# DaughterBoard.net
KiCad netlist of a schematic drawn in Altium Designer
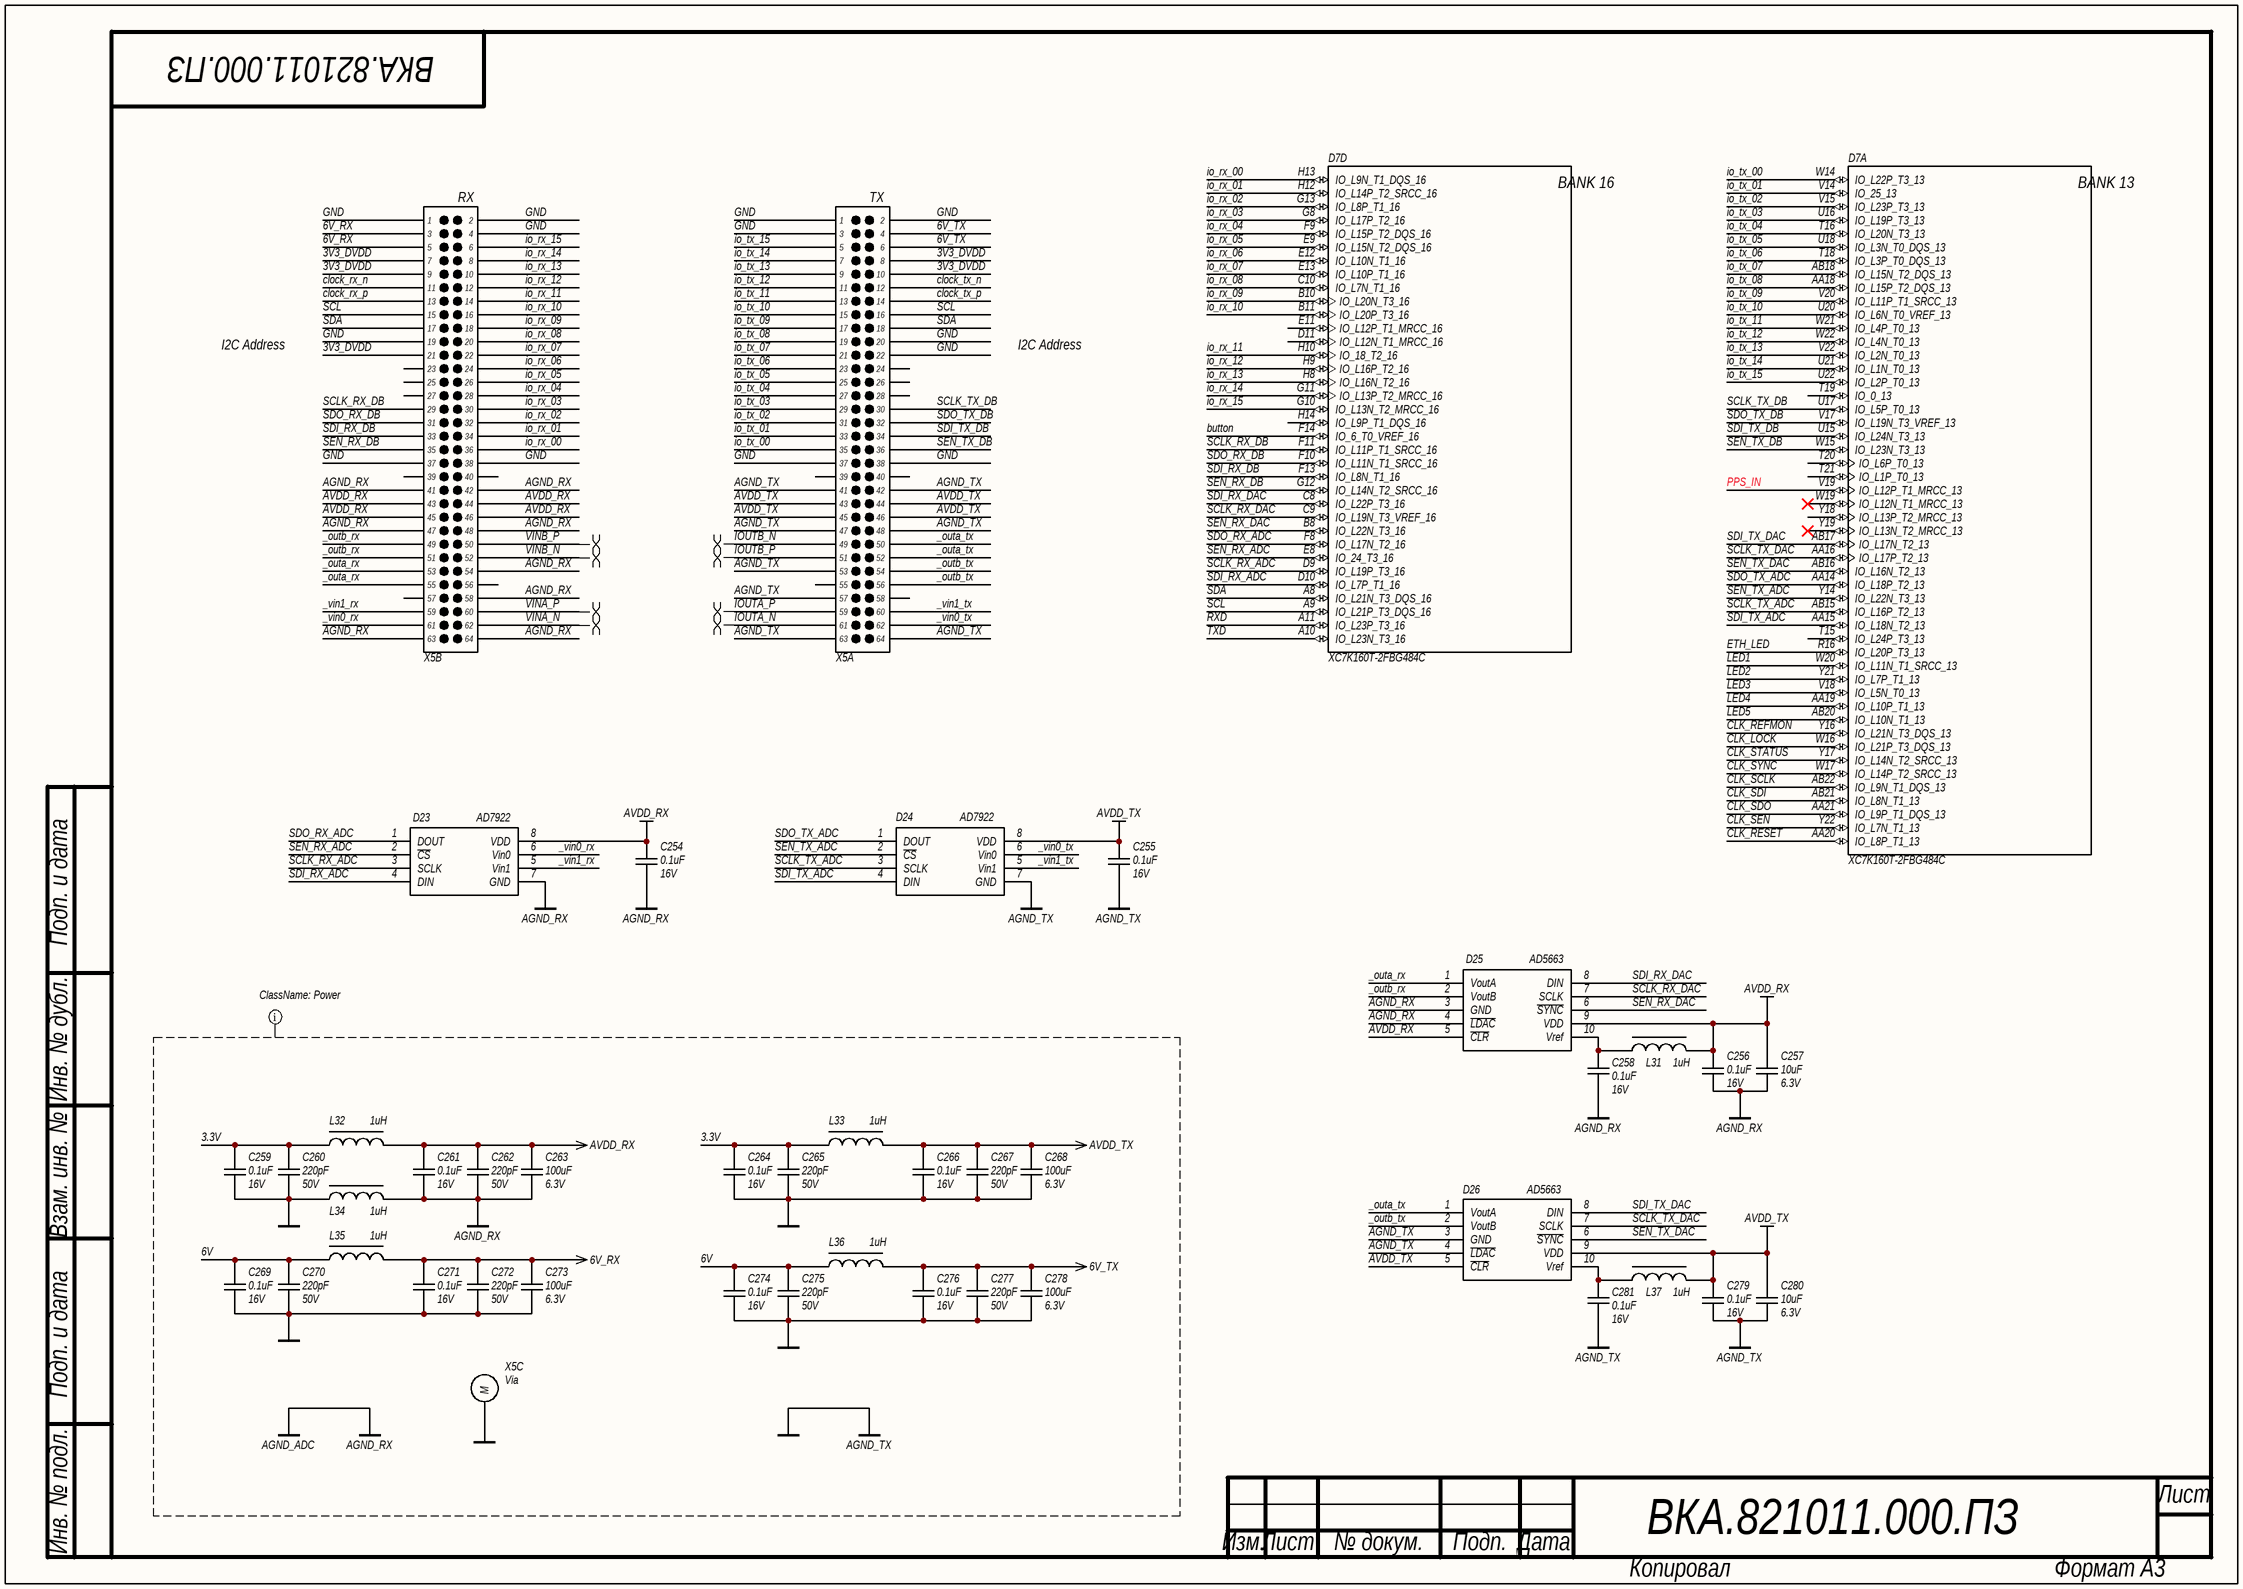
[diagram p0: DaughterBoard.SchDoc]

(export (version "E")
  (design (tool "Eeschema 10.0.6"))
  (components
    (comp (ref "C254")
      (value "0.1uF")
      (footprint "C0402")
      (description "SMD Capacitor")
      (fields
        (field (name "MANUFACTURER") "Murata")
        (field (name "TOLERANCE") "10%")
        (field (name "VOLTAGE") "16V")
      )
      (libsource (lib "Kintex_SDR") (part "CAP"))
    )
    (comp (ref "C255")
      (value "0.1uF")
      (footprint "C0402")
      (description "SMD Capacitor")
      (fields
        (field (name "MANUFACTURER") "Murata")
        (field (name "TOLERANCE") "10%")
        (field (name "VOLTAGE") "16V")
      )
      (libsource (lib "Kintex_SDR") (part "CAP"))
    )
    (comp (ref "C256")
      (value "0.1uF")
      (footprint "C0402")
      (description "SMD Capacitor")
      (fields
        (field (name "MANUFACTURER") "Murata")
        (field (name "TOLERANCE") "10%")
        (field (name "VOLTAGE") "16V")
      )
      (libsource (lib "Kintex_SDR") (part "CAP"))
    )
    (comp (ref "C257")
      (value "10uF")
      (footprint "C0603")
      (description "SMD Capacitor")
      (fields
        (field (name "MANUFACTURER") "Murata")
        (field (name "TOLERANCE") "10%")
        (field (name "VOLTAGE") "6.3V")
      )
      (libsource (lib "Kintex_SDR") (part "CAP"))
    )
    (comp (ref "C258")
      (value "0.1uF")
      (footprint "C0402")
      (description "SMD Capacitor")
      (fields
        (field (name "MANUFACTURER") "Murata")
        (field (name "TOLERANCE") "10%")
        (field (name "VOLTAGE") "16V")
      )
      (libsource (lib "Kintex_SDR") (part "CAP"))
    )
    (comp (ref "C259")
      (value "0.1uF")
      (footprint "C0603")
      (description "SMD Capacitor")
      (fields
        (field (name "MANUFACTURER") "Murata")
        (field (name "TOLERANCE") "10%")
        (field (name "VOLTAGE") "16V")
      )
      (libsource (lib "Kintex_SDR") (part "CAP"))
    )
    (comp (ref "C260")
      (value "220pF")
      (footprint "C0603")
      (description "SMD Capacitor")
      (fields
        (field (name "MANUFACTURER") "Murata")
        (field (name "TOLERANCE") "10%")
        (field (name "VOLTAGE") "50V")
      )
      (libsource (lib "Kintex_SDR") (part "CAP"))
    )
    (comp (ref "C261")
      (value "0.1uF")
      (footprint "C0603")
      (description "SMD Capacitor")
      (fields
        (field (name "MANUFACTURER") "Murata")
        (field (name "TOLERANCE") "10%")
        (field (name "VOLTAGE") "16V")
      )
      (libsource (lib "Kintex_SDR") (part "CAP"))
    )
    (comp (ref "C262")
      (value "220pF")
      (footprint "C0603")
      (description "SMD Capacitor")
      (fields
        (field (name "MANUFACTURER") "Murata")
        (field (name "TOLERANCE") "10%")
        (field (name "VOLTAGE") "50V")
      )
      (libsource (lib "Kintex_SDR") (part "CAP"))
    )
    (comp (ref "C263")
      (value "100uF")
      (footprint "C1210")
      (description "SMD Capacitor")
      (fields
        (field (name "MANUFACTURER") "Murata")
        (field (name "TOLERANCE") "20%")
        (field (name "VOLTAGE") "6.3V")
      )
      (libsource (lib "Kintex_SDR") (part "CAP uF"))
    )
    (comp (ref "C264")
      (value "0.1uF")
      (footprint "C0603")
      (description "SMD Capacitor")
      (fields
        (field (name "MANUFACTURER") "Murata")
        (field (name "TOLERANCE") "10%")
        (field (name "VOLTAGE") "16V")
      )
      (libsource (lib "Kintex_SDR") (part "CAP"))
    )
    (comp (ref "C265")
      (value "220pF")
      (footprint "C0603")
      (description "SMD Capacitor")
      (fields
        (field (name "MANUFACTURER") "Murata")
        (field (name "TOLERANCE") "10%")
        (field (name "VOLTAGE") "50V")
      )
      (libsource (lib "Kintex_SDR") (part "CAP"))
    )
    (comp (ref "C266")
      (value "0.1uF")
      (footprint "C0603")
      (description "SMD Capacitor")
      (fields
        (field (name "MANUFACTURER") "Murata")
        (field (name "TOLERANCE") "10%")
        (field (name "VOLTAGE") "16V")
      )
      (libsource (lib "Kintex_SDR") (part "CAP"))
    )
    (comp (ref "C267")
      (value "220pF")
      (footprint "C0603")
      (description "SMD Capacitor")
      (fields
        (field (name "MANUFACTURER") "Murata")
        (field (name "TOLERANCE") "10%")
        (field (name "VOLTAGE") "50V")
      )
      (libsource (lib "Kintex_SDR") (part "CAP"))
    )
    (comp (ref "C268")
      (value "100uF")
      (footprint "C1210")
      (description "SMD Capacitor")
      (fields
        (field (name "MANUFACTURER") "Murata")
        (field (name "TOLERANCE") "20%")
        (field (name "VOLTAGE") "6.3V")
      )
      (libsource (lib "Kintex_SDR") (part "CAP uF"))
    )
    (comp (ref "C269")
      (value "0.1uF")
      (footprint "C0603")
      (description "SMD Capacitor")
      (fields
        (field (name "MANUFACTURER") "Murata")
        (field (name "TOLERANCE") "10%")
        (field (name "VOLTAGE") "16V")
      )
      (libsource (lib "Kintex_SDR") (part "CAP"))
    )
    (comp (ref "C270")
      (value "220pF")
      (footprint "C0603")
      (description "SMD Capacitor")
      (fields
        (field (name "MANUFACTURER") "Murata")
        (field (name "TOLERANCE") "10%")
        (field (name "VOLTAGE") "50V")
      )
      (libsource (lib "Kintex_SDR") (part "CAP"))
    )
    (comp (ref "C271")
      (value "0.1uF")
      (footprint "C0603")
      (description "SMD Capacitor")
      (fields
        (field (name "MANUFACTURER") "Murata")
        (field (name "TOLERANCE") "10%")
        (field (name "VOLTAGE") "16V")
      )
      (libsource (lib "Kintex_SDR") (part "CAP"))
    )
    (comp (ref "C272")
      (value "220pF")
      (footprint "C0603")
      (description "SMD Capacitor")
      (fields
        (field (name "MANUFACTURER") "Murata")
        (field (name "TOLERANCE") "10%")
        (field (name "VOLTAGE") "50V")
      )
      (libsource (lib "Kintex_SDR") (part "CAP"))
    )
    (comp (ref "C273")
      (value "100uF")
      (footprint "C1210")
      (description "SMD Capacitor")
      (fields
        (field (name "MANUFACTURER") "Murata")
        (field (name "TOLERANCE") "20%")
        (field (name "VOLTAGE") "6.3V")
      )
      (libsource (lib "Kintex_SDR") (part "CAP uF"))
    )
    (comp (ref "C274")
      (value "0.1uF")
      (footprint "C0603")
      (description "SMD Capacitor")
      (fields
        (field (name "MANUFACTURER") "Murata")
        (field (name "TOLERANCE") "10%")
        (field (name "VOLTAGE") "16V")
      )
      (libsource (lib "Kintex_SDR") (part "CAP"))
    )
    (comp (ref "C275")
      (value "220pF")
      (footprint "C0603")
      (description "SMD Capacitor")
      (fields
        (field (name "MANUFACTURER") "Murata")
        (field (name "TOLERANCE") "10%")
        (field (name "VOLTAGE") "50V")
      )
      (libsource (lib "Kintex_SDR") (part "CAP"))
    )
    (comp (ref "C276")
      (value "0.1uF")
      (footprint "C0603")
      (description "SMD Capacitor")
      (fields
        (field (name "MANUFACTURER") "Murata")
        (field (name "TOLERANCE") "10%")
        (field (name "VOLTAGE") "16V")
      )
      (libsource (lib "Kintex_SDR") (part "CAP"))
    )
    (comp (ref "C277")
      (value "220pF")
      (footprint "C0603")
      (description "SMD Capacitor")
      (fields
        (field (name "MANUFACTURER") "Murata")
        (field (name "TOLERANCE") "10%")
        (field (name "VOLTAGE") "50V")
      )
      (libsource (lib "Kintex_SDR") (part "CAP"))
    )
    (comp (ref "C278")
      (value "100uF")
      (footprint "C1210")
      (description "SMD Capacitor")
      (fields
        (field (name "MANUFACTURER") "Murata")
        (field (name "TOLERANCE") "20%")
        (field (name "VOLTAGE") "6.3V")
      )
      (libsource (lib "Kintex_SDR") (part "CAP uF"))
    )
    (comp (ref "C279")
      (value "0.1uF")
      (footprint "C0402")
      (description "SMD Capacitor")
      (fields
        (field (name "MANUFACTURER") "Murata")
        (field (name "TOLERANCE") "10%")
        (field (name "VOLTAGE") "16V")
      )
      (libsource (lib "Kintex_SDR") (part "CAP"))
    )
    (comp (ref "C280")
      (value "10uF")
      (footprint "C0603")
      (description "SMD Capacitor")
      (fields
        (field (name "MANUFACTURER") "Murata")
        (field (name "TOLERANCE") "10%")
        (field (name "VOLTAGE") "6.3V")
      )
      (libsource (lib "Kintex_SDR") (part "CAP"))
    )
    (comp (ref "C281")
      (value "0.1uF")
      (footprint "C0402")
      (description "SMD Capacitor")
      (fields
        (field (name "MANUFACTURER") "Murata")
        (field (name "TOLERANCE") "10%")
        (field (name "VOLTAGE") "16V")
      )
      (libsource (lib "Kintex_SDR") (part "CAP"))
    )
    (comp (ref "D7")
      (value "XC7K160T-2FBG484C")
      (footprint "FBG484")
      (description "Xilinx 7-Series FPGA")
      (fields (field (name "MANUFACTURER") "Xilinx"))
      (libsource (lib "") (part "XC7K160T-2FBG484C_1"))
    )
    (comp (ref "D23")
      (value "AD7922")
      (footprint "MSOP-8")
      (description "1 MSPS, 10-/12-Bit ADC")
      (fields (field (name "MANUFACTURER") "Analog Device") (field (name "VOLTAGE") "2.35 V to 5.25 V"))
      (libsource (lib "Kintex_SDR") (part "AD79x2"))
    )
    (comp (ref "D24")
      (value "AD7922")
      (footprint "MSOP-8")
      (description "1 MSPS, 10-/12-Bit ADC")
      (fields (field (name "MANUFACTURER") "Analog Device") (field (name "VOLTAGE") "2.35 V to 5.25 V"))
      (libsource (lib "Kintex_SDR") (part "AD79x2"))
    )
    (comp (ref "D25")
      (value "AD5663")
      (footprint "MSOP-10")
      (description "Dual 12-/14-/16-Bit nanoDAC")
      (fields (field (name "MANUFACTURER") "Analog Device") (field (name "VOLTAGE") "2.7 V to 5.5 V"))
      (libsource (lib "Kintex_SDR") (part "AD56x3R"))
    )
    (comp (ref "D26")
      (value "AD5663")
      (footprint "MSOP-10")
      (description "Dual 12-/14-/16-Bit nanoDAC")
      (fields (field (name "MANUFACTURER") "Analog Device") (field (name "VOLTAGE") "2.7 V to 5.5 V"))
      (libsource (lib "Kintex_SDR") (part "AD56x3R"))
    )
    (comp (ref "L31")
      (value "1uH")
      (footprint "L1206_Murata")
      (description "Inductor Power Lines")
      (fields (field (name "MANUFACTURER") "Murata") (field (name "TOLERANCE") "5%"))
      (libsource (lib "Kintex_SDR") (part "Inductor LF"))
    )
    (comp (ref "L32")
      (value "1uH")
      (footprint "L1210_Murata LQH")
      (description "Inductor Power Lines")
      (fields (field (name "MANUFACTURER") "Murata") (field (name "TOLERANCE") "5%"))
      (libsource (lib "Kintex_SDR") (part "Inductor LF"))
    )
    (comp (ref "L33")
      (value "1uH")
      (footprint "L1210_Murata LQH")
      (description "Inductor Power Lines")
      (fields (field (name "MANUFACTURER") "Murata") (field (name "TOLERANCE") "5%"))
      (libsource (lib "Kintex_SDR") (part "Inductor LF"))
    )
    (comp (ref "L34")
      (value "1uH")
      (footprint "L1210_Murata LQH")
      (description "Inductor Power Lines")
      (fields (field (name "MANUFACTURER") "Murata") (field (name "TOLERANCE") "5%"))
      (libsource (lib "Kintex_SDR") (part "Inductor LF"))
    )
    (comp (ref "L35")
      (value "1uH")
      (footprint "L1210_Murata LQH")
      (description "Inductor Power Lines")
      (fields (field (name "MANUFACTURER") "Murata") (field (name "TOLERANCE") "5%"))
      (libsource (lib "Kintex_SDR") (part "Inductor LF"))
    )
    (comp (ref "L36")
      (value "1uH")
      (footprint "L1210_Murata LQH")
      (description "Inductor Power Lines")
      (fields (field (name "MANUFACTURER") "Murata") (field (name "TOLERANCE") "5%"))
      (libsource (lib "Kintex_SDR") (part "Inductor LF"))
    )
    (comp (ref "L37")
      (value "1uH")
      (footprint "L1206_Murata")
      (description "Inductor Power Lines")
      (fields (field (name "MANUFACTURER") "Murata") (field (name "TOLERANCE") "5%"))
      (libsource (lib "Kintex_SDR") (part "Inductor LF"))
    )
    (comp (ref "X5")
      (value "Via")
      (footprint "DBoard")
      (description "USRP DBoard")
      (libsource (lib "Kintex_SDR") (part "DBoard"))
    )
  )
  (nets
    (net (code "1") (name "/3.3V") (class "Default")
      (node (ref "C259") (pin "2") (pinfunction "2_2") (pintype "passive"))
      (node (ref "C260") (pin "2") (pinfunction "2_2") (pintype "passive"))
      (node (ref "C264") (pin "2") (pinfunction "2_2") (pintype "passive"))
      (node (ref "C265") (pin "2") (pinfunction "2_2") (pintype "passive"))
      (node (ref "L32") (pin "1") (pinfunction "1_1") (pintype "passive"))
      (node (ref "L33") (pin "1") (pinfunction "1_1") (pintype "passive"))
    )
    (net (code "2") (name "/3V3_DVDD") (class "Default")
      (node (ref "X5") (pin "10") (pinfunction "10_10") (pintype "passive"))
      (node (ref "X5") (pin "71") (pinfunction "7_71") (pintype "passive"))
      (node (ref "X5") (pin "73") (pinfunction "9_73") (pintype "passive"))
      (node (ref "X5") (pin "8") (pinfunction "8_8") (pintype "passive"))
      (node (ref "X5") (pin "85") (pinfunction "21_85") (pintype "passive"))
    )
    (net (code "3") (name "/6V") (class "Default")
      (node (ref "C269") (pin "2") (pinfunction "2_2") (pintype "passive"))
      (node (ref "C270") (pin "2") (pinfunction "2_2") (pintype "passive"))
      (node (ref "C274") (pin "2") (pinfunction "2_2") (pintype "passive"))
      (node (ref "C275") (pin "2") (pinfunction "2_2") (pintype "passive"))
      (node (ref "L35") (pin "1") (pinfunction "1_1") (pintype "passive"))
      (node (ref "L36") (pin "1") (pinfunction "1_1") (pintype "passive"))
    )
    (net (code "4") (name "/CLK_LOCK") (class "Default")
      (node (ref "D7") (pin "W16") (pinfunction "IO_L21P_T3_DQS_13_W16") (pintype "bidirectional"))
    )
    (net (code "5") (name "/CLK_REFMON") (class "Default")
      (node (ref "D7") (pin "Y16") (pinfunction "IO_L21N_T3_DQS_13_Y16") (pintype "bidirectional"))
    )
    (net (code "6") (name "/CLK_RESET") (class "Default")
      (node (ref "D7") (pin "AA20") (pinfunction "IO_L8P_T1_13_AA20") (pintype "bidirectional"))
    )
    (net (code "7") (name "/CLK_SCLK") (class "Default")
      (node (ref "D7") (pin "AB22") (pinfunction "IO_L9N_T1_DQS_13_AB22") (pintype "bidirectional"))
    )
    (net (code "8") (name "/CLK_SDI") (class "Default")
      (node (ref "D7") (pin "AB21") (pinfunction "IO_L8N_T1_13_AB21") (pintype "bidirectional"))
    )
    (net (code "9") (name "/CLK_SDO") (class "Default")
      (node (ref "D7") (pin "AA21") (pinfunction "IO_L9P_T1_DQS_13_AA21") (pintype "bidirectional"))
    )
    (net (code "10") (name "/CLK_SEN") (class "Default")
      (node (ref "D7") (pin "Y22") (pinfunction "IO_L7N_T1_13_Y22") (pintype "bidirectional"))
    )
    (net (code "11") (name "/CLK_STATUS") (class "Default")
      (node (ref "D7") (pin "Y17") (pinfunction "IO_L14N_T2_SRCC_13_Y17") (pintype "bidirectional"))
    )
    (net (code "12") (name "/CLK_SYNC") (class "Default")
      (node (ref "D7") (pin "W17") (pinfunction "IO_L14P_T2_SRCC_13_W17") (pintype "bidirectional"))
    )
    (net (code "13") (name "/ETH_LED") (class "Default")
      (node (ref "D7") (pin "R16") (pinfunction "IO_L20P_T3_13_R16") (pintype "bidirectional"))
    )
    (net (code "14") (name "/IOUTA_N") (class "Default")
      (node (ref "X5") (pin "61") (pinfunction "61_61") (pintype "passive"))
    )
    (net (code "15") (name "/IOUTA_P") (class "Default")
      (node (ref "X5") (pin "59") (pinfunction "59_59") (pintype "passive"))
    )
    (net (code "16") (name "/IOUTB_N") (class "Default")
      (node (ref "X5") (pin "49") (pinfunction "49_49") (pintype "passive"))
    )
    (net (code "17") (name "/IOUTB_P") (class "Default")
      (node (ref "X5") (pin "51") (pinfunction "51_51") (pintype "passive"))
    )
    (net (code "18") (name "/LED1") (class "Default")
      (node (ref "D7") (pin "W20") (pinfunction "IO_L11N_T1_SRCC_13_W20") (pintype "bidirectional"))
    )
    (net (code "19") (name "/LED2") (class "Default")
      (node (ref "D7") (pin "Y21") (pinfunction "IO_L7P_T1_13_Y21") (pintype "bidirectional"))
    )
    (net (code "20") (name "/LED3") (class "Default")
      (node (ref "D7") (pin "V18") (pinfunction "IO_L5N_T0_13_V18") (pintype "bidirectional"))
    )
    (net (code "21") (name "/LED4") (class "Default")
      (node (ref "D7") (pin "AA19") (pinfunction "IO_L10P_T1_13_AA19") (pintype "bidirectional"))
    )
    (net (code "22") (name "/LED5") (class "Default")
      (node (ref "D7") (pin "AB20") (pinfunction "IO_L10N_T1_13_AB20") (pintype "bidirectional"))
    )
    (net (code "23") (name "/PPS_IN") (class "Default")
      (node (ref "D7") (pin "V19") (pinfunction "IO_L12P_T1_MRCC_13_V19") (pintype "bidirectional"))
    )
    (net (code "24") (name "/RXD") (class "Default")
      (node (ref "D7") (pin "A11") (pinfunction "IO_L23P_T3_16_A11") (pintype "bidirectional"))
    )
    (net (code "25") (name "/SCL") (class "Default")
      (node (ref "D7") (pin "A9") (pinfunction "IO_L21P_T3_DQS_16_A9") (pintype "bidirectional"))
      (node (ref "X5") (pin "16") (pinfunction "16_16") (pintype "passive"))
      (node (ref "X5") (pin "79") (pinfunction "15_79") (pintype "passive"))
    )
    (net (code "26") (name "/SCLK_RX_ADC") (class "Default")
      (node (ref "D23") (pin "3") (pinfunction "SCLK_3") (pintype "passive"))
      (node (ref "D7") (pin "D9") (pinfunction "IO_L19P_T3_16_D9") (pintype "bidirectional"))
    )
    (net (code "27") (name "/SCLK_RX_DAC") (class "Default")
      (node (ref "D25") (pin "7") (pinfunction "SCLK_7") (pintype "passive"))
      (node (ref "D7") (pin "C9") (pinfunction "IO_L19N_T3_VREF_16_C9") (pintype "bidirectional"))
    )
    (net (code "28") (name "/SCLK_RX_DB") (class "Default")
      (node (ref "D7") (pin "F11") (pinfunction "IO_L11P_T1_SRCC_16_F11") (pintype "bidirectional"))
      (node (ref "X5") (pin "93") (pinfunction "29_93") (pintype "passive"))
    )
    (net (code "29") (name "/SCLK_TX_ADC") (class "Default")
      (node (ref "D24") (pin "3") (pinfunction "SCLK_3") (pintype "passive"))
      (node (ref "D7") (pin "AB15") (pinfunction "IO_L16P_T2_13_AB15") (pintype "bidirectional"))
    )
    (net (code "30") (name "/SCLK_TX_DAC") (class "Default")
      (node (ref "D26") (pin "7") (pinfunction "SCLK_7") (pintype "passive"))
      (node (ref "D7") (pin "AA16") (pinfunction "IO_L17P_T2_13_AA16") (pintype "bidirectional"))
    )
    (net (code "31") (name "/SCLK_TX_DB") (class "Default")
      (node (ref "D7") (pin "U17") (pinfunction "IO_L5P_T0_13_U17") (pintype "bidirectional"))
      (node (ref "X5") (pin "30") (pinfunction "30_30") (pintype "passive"))
    )
    (net (code "32") (name "/SDA") (class "Default")
      (node (ref "D7") (pin "A8") (pinfunction "IO_L21N_T3_DQS_16_A8") (pintype "bidirectional"))
      (node (ref "X5") (pin "18") (pinfunction "18_18") (pintype "passive"))
      (node (ref "X5") (pin "81") (pinfunction "17_81") (pintype "passive"))
    )
    (net (code "33") (name "/SDI_RX_ADC") (class "Default")
      (node (ref "D23") (pin "4") (pinfunction "DIN_4") (pintype "passive"))
      (node (ref "D7") (pin "D10") (pinfunction "IO_L7P_T1_16_D10") (pintype "bidirectional"))
    )
    (net (code "34") (name "/SDI_RX_DAC") (class "Default")
      (node (ref "D25") (pin "8") (pinfunction "DIN_8") (pintype "passive"))
      (node (ref "D7") (pin "C8") (pinfunction "IO_L22P_T3_16_C8") (pintype "bidirectional"))
    )
    (net (code "35") (name "/SDI_RX_DB") (class "Default")
      (node (ref "D7") (pin "F13") (pinfunction "IO_L8N_T1_16_F13") (pintype "bidirectional"))
      (node (ref "X5") (pin "97") (pinfunction "33_97") (pintype "passive"))
    )
    (net (code "36") (name "/SDI_TX_ADC") (class "Default")
      (node (ref "D24") (pin "4") (pinfunction "DIN_4") (pintype "passive"))
      (node (ref "D7") (pin "AA15") (pinfunction "IO_L18N_T2_13_AA15") (pintype "bidirectional"))
    )
    (net (code "37") (name "/SDI_TX_DAC") (class "Default")
      (node (ref "D26") (pin "8") (pinfunction "DIN_8") (pintype "passive"))
      (node (ref "D7") (pin "AB17") (pinfunction "IO_L17N_T2_13_AB17") (pintype "bidirectional"))
    )
    (net (code "38") (name "/SDI_TX_DB") (class "Default")
      (node (ref "D7") (pin "U15") (pinfunction "IO_L24N_T3_13_U15") (pintype "bidirectional"))
      (node (ref "X5") (pin "34") (pinfunction "34_34") (pintype "passive"))
    )
    (net (code "39") (name "/SDO_RX_ADC") (class "Default")
      (node (ref "D23") (pin "1") (pinfunction "DOUT_1") (pintype "passive"))
      (node (ref "D7") (pin "F8") (pinfunction "IO_L17N_T2_16_F8") (pintype "bidirectional"))
    )
    (net (code "40") (name "/SDO_RX_DB") (class "Default")
      (node (ref "D7") (pin "F10") (pinfunction "IO_L11N_T1_SRCC_16_F10") (pintype "bidirectional"))
      (node (ref "X5") (pin "95") (pinfunction "31_95") (pintype "passive"))
    )
    (net (code "41") (name "/SDO_TX_ADC") (class "Default")
      (node (ref "D24") (pin "1") (pinfunction "DOUT_1") (pintype "passive"))
      (node (ref "D7") (pin "AA14") (pinfunction "IO_L18P_T2_13_AA14") (pintype "bidirectional"))
    )
    (net (code "42") (name "/SDO_TX_DB") (class "Default")
      (node (ref "D7") (pin "V17") (pinfunction "IO_L19N_T3_VREF_13_V17") (pintype "bidirectional"))
      (node (ref "X5") (pin "32") (pinfunction "32_32") (pintype "passive"))
    )
    (net (code "43") (name "/SEN_RX_ADC") (class "Default")
      (node (ref "D23") (pin "2") (pinfunction "~{CS}_2") (pintype "passive"))
      (node (ref "D7") (pin "E8") (pinfunction "IO_24_T3_16_E8") (pintype "bidirectional"))
    )
    (net (code "44") (name "/SEN_RX_DAC") (class "Default")
      (node (ref "D25") (pin "6") (pinfunction "~{SYNC}_6") (pintype "passive"))
      (node (ref "D7") (pin "B8") (pinfunction "IO_L22N_T3_16_B8") (pintype "bidirectional"))
    )
    (net (code "45") (name "/SEN_RX_DB") (class "Default")
      (node (ref "D7") (pin "G12") (pinfunction "IO_L14N_T2_SRCC_16_G12") (pintype "bidirectional"))
      (node (ref "X5") (pin "99") (pinfunction "35_99") (pintype "passive"))
    )
    (net (code "46") (name "/SEN_TX_ADC") (class "Default")
      (node (ref "D24") (pin "2") (pinfunction "~{CS}_2") (pintype "passive"))
      (node (ref "D7") (pin "Y14") (pinfunction "IO_L22N_T3_13_Y14") (pintype "bidirectional"))
    )
    (net (code "47") (name "/SEN_TX_DAC") (class "Default")
      (node (ref "D26") (pin "6") (pinfunction "~{SYNC}_6") (pintype "passive"))
      (node (ref "D7") (pin "AB16") (pinfunction "IO_L16N_T2_13_AB16") (pintype "bidirectional"))
    )
    (net (code "48") (name "/SEN_TX_DB") (class "Default")
      (node (ref "D7") (pin "W15") (pinfunction "IO_L23N_T3_13_W15") (pintype "bidirectional"))
      (node (ref "X5") (pin "36") (pinfunction "36_36") (pintype "passive"))
    )
    (net (code "49") (name "/TXD") (class "Default")
      (node (ref "D7") (pin "A10") (pinfunction "IO_L23N_T3_16_A10") (pintype "bidirectional"))
    )
    (net (code "50") (name "/VINA_N") (class "Default")
      (node (ref "X5") (pin "126") (pinfunction "62_126") (pintype "passive"))
    )
    (net (code "51") (name "/VINA_P") (class "Default")
      (node (ref "X5") (pin "124") (pinfunction "60_124") (pintype "passive"))
    )
    (net (code "52") (name "/VINB_N") (class "Default")
      (node (ref "X5") (pin "116") (pinfunction "52_116") (pintype "passive"))
    )
    (net (code "53") (name "/VINB_P") (class "Default")
      (node (ref "X5") (pin "114") (pinfunction "50_114") (pintype "passive"))
    )
    (net (code "54") (name "/_outa_rx") (class "Default")
      (node (ref "D25") (pin "1") (pinfunction "VoutA_1") (pintype "passive"))
      (node (ref "X5") (pin "117") (pinfunction "53_117") (pintype "passive"))
      (node (ref "X5") (pin "119") (pinfunction "55_119") (pintype "passive"))
    )
    (net (code "55") (name "/_outa_tx") (class "Default")
      (node (ref "D26") (pin "1") (pinfunction "VoutA_1") (pintype "passive"))
      (node (ref "X5") (pin "50") (pinfunction "50_50") (pintype "passive"))
      (node (ref "X5") (pin "52") (pinfunction "52_52") (pintype "passive"))
    )
    (net (code "56") (name "/_outb_rx") (class "Default")
      (node (ref "D25") (pin "2") (pinfunction "VoutB_2") (pintype "passive"))
      (node (ref "X5") (pin "113") (pinfunction "49_113") (pintype "passive"))
      (node (ref "X5") (pin "115") (pinfunction "51_115") (pintype "passive"))
    )
    (net (code "57") (name "/_outb_tx") (class "Default")
      (node (ref "D26") (pin "2") (pinfunction "VoutB_2") (pintype "passive"))
      (node (ref "X5") (pin "54") (pinfunction "54_54") (pintype "passive"))
      (node (ref "X5") (pin "56") (pinfunction "56_56") (pintype "passive"))
    )
    (net (code "58") (name "/_vin0_rx") (class "Default")
      (node (ref "D23") (pin "6") (pinfunction "Vin0_6") (pintype "passive"))
      (node (ref "X5") (pin "125") (pinfunction "61_125") (pintype "passive"))
    )
    (net (code "59") (name "/_vin0_tx") (class "Default")
      (node (ref "D24") (pin "6") (pinfunction "Vin0_6") (pintype "passive"))
      (node (ref "X5") (pin "62") (pinfunction "62_62") (pintype "passive"))
    )
    (net (code "60") (name "/_vin1_rx") (class "Default")
      (node (ref "D23") (pin "5") (pinfunction "Vin1_5") (pintype "passive"))
      (node (ref "X5") (pin "123") (pinfunction "59_123") (pintype "passive"))
    )
    (net (code "61") (name "/_vin1_tx") (class "Default")
      (node (ref "D24") (pin "5") (pinfunction "Vin1_5") (pintype "passive"))
      (node (ref "X5") (pin "60") (pinfunction "60_60") (pintype "passive"))
    )
    (net (code "62") (name "/button") (class "Default")
      (node (ref "D7") (pin "F14") (pinfunction "IO_6_T0_VREF_16_F14") (pintype "bidirectional"))
    )
    (net (code "63") (name "/clock_rx_n") (class "Default")
      (node (ref "X5") (pin "75") (pinfunction "11_75") (pintype "passive"))
    )
    (net (code "64") (name "/clock_rx_p") (class "Default")
      (node (ref "X5") (pin "77") (pinfunction "13_77") (pintype "passive"))
    )
    (net (code "65") (name "/clock_tx_n") (class "Default")
      (node (ref "X5") (pin "12") (pinfunction "12_12") (pintype "passive"))
    )
    (net (code "66") (name "/clock_tx_p") (class "Default")
      (node (ref "X5") (pin "14") (pinfunction "14_14") (pintype "passive"))
    )
    (net (code "67") (name "/io_rx_00") (class "Default")
      (node (ref "D7") (pin "H13") (pinfunction "IO_L9N_T1_DQS_16_H13") (pintype "bidirectional"))
      (node (ref "X5") (pin "100") (pinfunction "36_100") (pintype "passive"))
    )
    (net (code "68") (name "/io_rx_01") (class "Default")
      (node (ref "D7") (pin "H12") (pinfunction "IO_L14P_T2_SRCC_16_H12") (pintype "bidirectional"))
      (node (ref "X5") (pin "98") (pinfunction "34_98") (pintype "passive"))
    )
    (net (code "69") (name "/io_rx_02") (class "Default")
      (node (ref "D7") (pin "G13") (pinfunction "IO_L8P_T1_16_G13") (pintype "bidirectional"))
      (node (ref "X5") (pin "96") (pinfunction "32_96") (pintype "passive"))
    )
    (net (code "70") (name "/io_rx_03") (class "Default")
      (node (ref "D7") (pin "G8") (pinfunction "IO_L17P_T2_16_G8") (pintype "bidirectional"))
      (node (ref "X5") (pin "94") (pinfunction "30_94") (pintype "passive"))
    )
    (net (code "71") (name "/io_rx_04") (class "Default")
      (node (ref "D7") (pin "F9") (pinfunction "IO_L15P_T2_DQS_16_F9") (pintype "bidirectional"))
      (node (ref "X5") (pin "92") (pinfunction "28_92") (pintype "passive"))
    )
    (net (code "72") (name "/io_rx_05") (class "Default")
      (node (ref "D7") (pin "E9") (pinfunction "IO_L15N_T2_DQS_16_E9") (pintype "bidirectional"))
      (node (ref "X5") (pin "90") (pinfunction "26_90") (pintype "passive"))
    )
    (net (code "73") (name "/io_rx_06") (class "Default")
      (node (ref "D7") (pin "E12") (pinfunction "IO_L10N_T1_16_E12") (pintype "bidirectional"))
      (node (ref "X5") (pin "88") (pinfunction "24_88") (pintype "passive"))
    )
    (net (code "74") (name "/io_rx_07") (class "Default")
      (node (ref "D7") (pin "E13") (pinfunction "IO_L10P_T1_16_E13") (pintype "bidirectional"))
      (node (ref "X5") (pin "86") (pinfunction "22_86") (pintype "passive"))
    )
    (net (code "75") (name "/io_rx_08") (class "Default")
      (node (ref "D7") (pin "C10") (pinfunction "IO_L7N_T1_16_C10") (pintype "bidirectional"))
      (node (ref "X5") (pin "84") (pinfunction "20_84") (pintype "passive"))
    )
    (net (code "76") (name "/io_rx_09") (class "Default")
      (node (ref "D7") (pin "B10") (pinfunction "IO_L20N_T3_16_B10") (pintype "bidirectional"))
      (node (ref "X5") (pin "82") (pinfunction "18_82") (pintype "passive"))
    )
    (net (code "77") (name "/io_rx_10") (class "Default")
      (node (ref "D7") (pin "B11") (pinfunction "IO_L20P_T3_16_B11") (pintype "bidirectional"))
      (node (ref "X5") (pin "80") (pinfunction "16_80") (pintype "passive"))
    )
    (net (code "78") (name "/io_rx_11") (class "Default")
      (node (ref "D7") (pin "H10") (pinfunction "IO_18_T2_16_H10") (pintype "bidirectional"))
      (node (ref "X5") (pin "78") (pinfunction "14_78") (pintype "passive"))
    )
    (net (code "79") (name "/io_rx_12") (class "Default")
      (node (ref "D7") (pin "H9") (pinfunction "IO_L16P_T2_16_H9") (pintype "bidirectional"))
      (node (ref "X5") (pin "76") (pinfunction "12_76") (pintype "passive"))
    )
    (net (code "80") (name "/io_rx_13") (class "Default")
      (node (ref "D7") (pin "H8") (pinfunction "IO_L16N_T2_16_H8") (pintype "bidirectional"))
      (node (ref "X5") (pin "74") (pinfunction "10_74") (pintype "passive"))
    )
    (net (code "81") (name "/io_rx_14") (class "Default")
      (node (ref "D7") (pin "G11") (pinfunction "IO_L13P_T2_MRCC_16_G11") (pintype "bidirectional"))
      (node (ref "X5") (pin "72") (pinfunction "8_72") (pintype "passive"))
    )
    (net (code "82") (name "/io_rx_15") (class "Default")
      (node (ref "D7") (pin "G10") (pinfunction "IO_L13N_T2_MRCC_16_G10") (pintype "bidirectional"))
      (node (ref "X5") (pin "70") (pinfunction "6_70") (pintype "passive"))
    )
    (net (code "83") (name "/io_tx_00") (class "Default")
      (node (ref "D7") (pin "W14") (pinfunction "IO_L22P_T3_13_W14") (pintype "bidirectional"))
      (node (ref "X5") (pin "35") (pinfunction "35_35") (pintype "passive"))
    )
    (net (code "84") (name "/io_tx_01") (class "Default")
      (node (ref "D7") (pin "V14") (pinfunction "IO_25_13_V14") (pintype "bidirectional"))
      (node (ref "X5") (pin "33") (pinfunction "33_33") (pintype "passive"))
    )
    (net (code "85") (name "/io_tx_02") (class "Default")
      (node (ref "D7") (pin "V15") (pinfunction "IO_L23P_T3_13_V15") (pintype "bidirectional"))
      (node (ref "X5") (pin "31") (pinfunction "31_31") (pintype "passive"))
    )
    (net (code "86") (name "/io_tx_03") (class "Default")
      (node (ref "D7") (pin "U16") (pinfunction "IO_L19P_T3_13_U16") (pintype "bidirectional"))
      (node (ref "X5") (pin "29") (pinfunction "29_29") (pintype "passive"))
    )
    (net (code "87") (name "/io_tx_04") (class "Default")
      (node (ref "D7") (pin "T16") (pinfunction "IO_L20N_T3_13_T16") (pintype "bidirectional"))
      (node (ref "X5") (pin "27") (pinfunction "27_27") (pintype "passive"))
    )
    (net (code "88") (name "/io_tx_05") (class "Default")
      (node (ref "D7") (pin "U18") (pinfunction "IO_L3N_T0_DQS_13_U18") (pintype "bidirectional"))
      (node (ref "X5") (pin "25") (pinfunction "25_25") (pintype "passive"))
    )
    (net (code "89") (name "/io_tx_06") (class "Default")
      (node (ref "D7") (pin "T18") (pinfunction "IO_L3P_T0_DQS_13_T18") (pintype "bidirectional"))
      (node (ref "X5") (pin "23") (pinfunction "23_23") (pintype "passive"))
    )
    (net (code "90") (name "/io_tx_07") (class "Default")
      (node (ref "D7") (pin "AB18") (pinfunction "IO_L15N_T2_DQS_13_AB18") (pintype "bidirectional"))
      (node (ref "X5") (pin "21") (pinfunction "21_21") (pintype "passive"))
    )
    (net (code "91") (name "/io_tx_08") (class "Default")
      (node (ref "D7") (pin "AA18") (pinfunction "IO_L15P_T2_DQS_13_AA18") (pintype "bidirectional"))
      (node (ref "X5") (pin "19") (pinfunction "19_19") (pintype "passive"))
    )
    (net (code "92") (name "/io_tx_09") (class "Default")
      (node (ref "D7") (pin "V20") (pinfunction "IO_L11P_T1_SRCC_13_V20") (pintype "bidirectional"))
      (node (ref "X5") (pin "17") (pinfunction "17_17") (pintype "passive"))
    )
    (net (code "93") (name "/io_tx_10") (class "Default")
      (node (ref "D7") (pin "U20") (pinfunction "IO_L6N_T0_VREF_13_U20") (pintype "bidirectional"))
      (node (ref "X5") (pin "15") (pinfunction "15_15") (pintype "passive"))
    )
    (net (code "94") (name "/io_tx_11") (class "Default")
      (node (ref "D7") (pin "W21") (pinfunction "IO_L4P_T0_13_W21") (pintype "bidirectional"))
      (node (ref "X5") (pin "13") (pinfunction "13_13") (pintype "passive"))
    )
    (net (code "95") (name "/io_tx_12") (class "Default")
      (node (ref "D7") (pin "W22") (pinfunction "IO_L4N_T0_13_W22") (pintype "bidirectional"))
      (node (ref "X5") (pin "11") (pinfunction "11_11") (pintype "passive"))
    )
    (net (code "96") (name "/io_tx_13") (class "Default")
      (node (ref "D7") (pin "V22") (pinfunction "IO_L2N_T0_13_V22") (pintype "bidirectional"))
      (node (ref "X5") (pin "9") (pinfunction "9_9") (pintype "passive"))
    )
    (net (code "97") (name "/io_tx_14") (class "Default")
      (node (ref "D7") (pin "U21") (pinfunction "IO_L1N_T0_13_U21") (pintype "bidirectional"))
      (node (ref "X5") (pin "7") (pinfunction "7_7") (pintype "passive"))
    )
    (net (code "98") (name "/io_tx_15") (class "Default")
      (node (ref "D7") (pin "U22") (pinfunction "IO_L2P_T0_13_U22") (pintype "bidirectional"))
      (node (ref "X5") (pin "5") (pinfunction "5_5") (pintype "passive"))
    )
    (net (code "99") (name "6V_RX") (class "Default")
      (node (ref "C271") (pin "2") (pinfunction "2_2") (pintype "passive"))
      (node (ref "C272") (pin "2") (pinfunction "2_2") (pintype "passive"))
      (node (ref "C273") (pin "2") (pinfunction "2_2") (pintype "passive"))
      (node (ref "L35") (pin "2") (pinfunction "2_2") (pintype "passive"))
      (node (ref "X5") (pin "67") (pinfunction "3_67") (pintype "passive"))
      (node (ref "X5") (pin "69") (pinfunction "5_69") (pintype "passive"))
    )
    (net (code "100") (name "6V_TX") (class "Default")
      (node (ref "C276") (pin "2") (pinfunction "2_2") (pintype "passive"))
      (node (ref "C277") (pin "2") (pinfunction "2_2") (pintype "passive"))
      (node (ref "C278") (pin "2") (pinfunction "2_2") (pintype "passive"))
      (node (ref "L36") (pin "2") (pinfunction "2_2") (pintype "passive"))
      (node (ref "X5") (pin "4") (pinfunction "4_4") (pintype "passive"))
      (node (ref "X5") (pin "6") (pinfunction "6_6") (pintype "passive"))
    )
    (net (code "101") (name "AGND_ADC") (class "Default")
      (node (ref "C254") (pin "1") (pinfunction "1_1") (pintype "passive"))
      (node (ref "C256") (pin "1") (pinfunction "1_1") (pintype "passive"))
      (node (ref "C257") (pin "1") (pinfunction "1_1") (pintype "passive"))
      (node (ref "C258") (pin "1") (pinfunction "1_1") (pintype "passive"))
      (node (ref "C261") (pin "1") (pinfunction "1_1") (pintype "passive"))
      (node (ref "C262") (pin "1") (pinfunction "1_1") (pintype "passive"))
      (node (ref "C263") (pin "1") (pinfunction "1_1") (pintype "passive"))
      (node (ref "D23") (pin "7") (pinfunction "GND_7") (pintype "passive"))
      (node (ref "D25") (pin "3") (pinfunction "GND_3") (pintype "passive"))
      (node (ref "D25") (pin "4") (pinfunction "~{LDAC}_4") (pintype "passive"))
      (node (ref "L34") (pin "2") (pinfunction "2_2") (pintype "passive"))
      (node (ref "X5") (pin "105") (pinfunction "41_105") (pintype "passive"))
      (node (ref "X5") (pin "106") (pinfunction "42_106") (pintype "passive"))
      (node (ref "X5") (pin "111") (pinfunction "47_111") (pintype "passive"))
      (node (ref "X5") (pin "112") (pinfunction "48_112") (pintype "passive"))
      (node (ref "X5") (pin "118") (pinfunction "54_118") (pintype "passive"))
      (node (ref "X5") (pin "122") (pinfunction "58_122") (pintype "passive"))
      (node (ref "X5") (pin "127") (pinfunction "63_127") (pintype "passive"))
      (node (ref "X5") (pin "128") (pinfunction "64_128") (pintype "passive"))
    )
    (net (code "102") (name "AGND_TX") (class "Default")
      (node (ref "C255") (pin "1") (pinfunction "1_1") (pintype "passive"))
      (node (ref "C259") (pin "1") (pinfunction "1_1") (pintype "passive"))
      (node (ref "C260") (pin "1") (pinfunction "1_1") (pintype "passive"))
      (node (ref "C264") (pin "1") (pinfunction "1_1") (pintype "passive"))
      (node (ref "C265") (pin "1") (pinfunction "1_1") (pintype "passive"))
      (node (ref "C266") (pin "1") (pinfunction "1_1") (pintype "passive"))
      (node (ref "C267") (pin "1") (pinfunction "1_1") (pintype "passive"))
      (node (ref "C268") (pin "1") (pinfunction "1_1") (pintype "passive"))
      (node (ref "C269") (pin "1") (pinfunction "1_1") (pintype "passive"))
      (node (ref "C270") (pin "1") (pinfunction "1_1") (pintype "passive"))
      (node (ref "C271") (pin "1") (pinfunction "1_1") (pintype "passive"))
      (node (ref "C272") (pin "1") (pinfunction "1_1") (pintype "passive"))
      (node (ref "C273") (pin "1") (pinfunction "1_1") (pintype "passive"))
      (node (ref "C274") (pin "1") (pinfunction "1_1") (pintype "passive"))
      (node (ref "C275") (pin "1") (pinfunction "1_1") (pintype "passive"))
      (node (ref "C276") (pin "1") (pinfunction "1_1") (pintype "passive"))
      (node (ref "C277") (pin "1") (pinfunction "1_1") (pintype "passive"))
      (node (ref "C278") (pin "1") (pinfunction "1_1") (pintype "passive"))
      (node (ref "C279") (pin "1") (pinfunction "1_1") (pintype "passive"))
      (node (ref "C280") (pin "1") (pinfunction "1_1") (pintype "passive"))
      (node (ref "C281") (pin "1") (pinfunction "1_1") (pintype "passive"))
      (node (ref "D24") (pin "7") (pinfunction "GND_7") (pintype "passive"))
      (node (ref "D26") (pin "3") (pinfunction "GND_3") (pintype "passive"))
      (node (ref "D26") (pin "4") (pinfunction "~{LDAC}_4") (pintype "passive"))
      (node (ref "L34") (pin "1") (pinfunction "1_1") (pintype "passive"))
      (node (ref "X5") (pin "0") (pinfunction "M_0") (pintype "passive"))
      (node (ref "X5") (pin "1") (pinfunction "1_1") (pintype "passive"))
      (node (ref "X5") (pin "101") (pinfunction "37_101") (pintype "passive"))
      (node (ref "X5") (pin "102") (pinfunction "38_102") (pintype "passive"))
      (node (ref "X5") (pin "2") (pinfunction "2_2") (pintype "passive"))
      (node (ref "X5") (pin "20") (pinfunction "20_20") (pintype "passive"))
      (node (ref "X5") (pin "22") (pinfunction "22_22") (pintype "passive"))
      (node (ref "X5") (pin "3") (pinfunction "3_3") (pintype "passive"))
      (node (ref "X5") (pin "37") (pinfunction "37_37") (pintype "passive"))
      (node (ref "X5") (pin "38") (pinfunction "38_38") (pintype "passive"))
      (node (ref "X5") (pin "41") (pinfunction "41_41") (pintype "passive"))
      (node (ref "X5") (pin "42") (pinfunction "42_42") (pintype "passive"))
      (node (ref "X5") (pin "47") (pinfunction "47_47") (pintype "passive"))
      (node (ref "X5") (pin "48") (pinfunction "48_48") (pintype "passive"))
      (node (ref "X5") (pin "53") (pinfunction "53_53") (pintype "passive"))
      (node (ref "X5") (pin "57") (pinfunction "57_57") (pintype "passive"))
      (node (ref "X5") (pin "63") (pinfunction "63_63") (pintype "passive"))
      (node (ref "X5") (pin "64") (pinfunction "64_64") (pintype "passive"))
      (node (ref "X5") (pin "65") (pinfunction "1_65") (pintype "passive"))
      (node (ref "X5") (pin "66") (pinfunction "2_66") (pintype "passive"))
      (node (ref "X5") (pin "68") (pinfunction "4_68") (pintype "passive"))
      (node (ref "X5") (pin "83") (pinfunction "19_83") (pintype "passive"))
    )
    (net (code "103") (name "AVDD_RX") (class "Default")
      (node (ref "C254") (pin "2") (pinfunction "2_2") (pintype "passive"))
      (node (ref "C256") (pin "2") (pinfunction "2_2") (pintype "passive"))
      (node (ref "C257") (pin "2") (pinfunction "2_2") (pintype "passive"))
      (node (ref "C261") (pin "2") (pinfunction "2_2") (pintype "passive"))
      (node (ref "C262") (pin "2") (pinfunction "2_2") (pintype "passive"))
      (node (ref "C263") (pin "2") (pinfunction "2_2") (pintype "passive"))
      (node (ref "D23") (pin "8") (pinfunction "VDD_8") (pintype "passive"))
      (node (ref "D25") (pin "5") (pinfunction "~{CLR}_5") (pintype "passive"))
      (node (ref "D25") (pin "9") (pinfunction "VDD_9") (pintype "passive"))
      (node (ref "L31") (pin "2") (pinfunction "2_2") (pintype "passive"))
      (node (ref "L32") (pin "2") (pinfunction "2_2") (pintype "passive"))
      (node (ref "X5") (pin "107") (pinfunction "43_107") (pintype "passive"))
      (node (ref "X5") (pin "108") (pinfunction "44_108") (pintype "passive"))
      (node (ref "X5") (pin "109") (pinfunction "45_109") (pintype "passive"))
      (node (ref "X5") (pin "110") (pinfunction "46_110") (pintype "passive"))
    )
    (net (code "104") (name "AVDD_TX") (class "Default")
      (node (ref "C255") (pin "2") (pinfunction "2_2") (pintype "passive"))
      (node (ref "C266") (pin "2") (pinfunction "2_2") (pintype "passive"))
      (node (ref "C267") (pin "2") (pinfunction "2_2") (pintype "passive"))
      (node (ref "C268") (pin "2") (pinfunction "2_2") (pintype "passive"))
      (node (ref "C279") (pin "2") (pinfunction "2_2") (pintype "passive"))
      (node (ref "C280") (pin "2") (pinfunction "2_2") (pintype "passive"))
      (node (ref "D24") (pin "8") (pinfunction "VDD_8") (pintype "passive"))
      (node (ref "D26") (pin "5") (pinfunction "~{CLR}_5") (pintype "passive"))
      (node (ref "D26") (pin "9") (pinfunction "VDD_9") (pintype "passive"))
      (node (ref "L33") (pin "2") (pinfunction "2_2") (pintype "passive"))
      (node (ref "L37") (pin "2") (pinfunction "2_2") (pintype "passive"))
      (node (ref "X5") (pin "43") (pinfunction "43_43") (pintype "passive"))
      (node (ref "X5") (pin "44") (pinfunction "44_44") (pintype "passive"))
      (node (ref "X5") (pin "45") (pinfunction "45_45") (pintype "passive"))
      (node (ref "X5") (pin "46") (pinfunction "46_46") (pintype "passive"))
    )
    (net (code "105") (name "Net-(D25-Vref)") (class "Default")
      (node (ref "C258") (pin "2") (pinfunction "2_2") (pintype "passive"))
      (node (ref "D25") (pin "10") (pinfunction "Vref_10") (pintype "passive"))
      (node (ref "L31") (pin "1") (pinfunction "1_1") (pintype "passive"))
    )
    (net (code "106") (name "Net-(D26-Vref)") (class "Default")
      (node (ref "C281") (pin "2") (pinfunction "2_2") (pintype "passive"))
      (node (ref "D26") (pin "10") (pinfunction "Vref_10") (pintype "passive"))
      (node (ref "L37") (pin "1") (pinfunction "1_1") (pintype "passive"))
    )
    (net (code "107") (name "unconnected-(D7A-IO_0_13-PadT19)") (class "Default")
      (node (ref "D7") (pin "T19") (pinfunction "IO_0_13_T19") (pintype "bidirectional"))
    )
    (net (code "108") (name "unconnected-(D7A-IO_L1P_T0_13-PadT21)") (class "Default")
      (node (ref "D7") (pin "T21") (pinfunction "IO_L1P_T0_13_T21") (pintype "bidirectional"))
    )
    (net (code "109") (name "unconnected-(D7A-IO_L6P_T0_13-PadT20)") (class "Default")
      (node (ref "D7") (pin "T20") (pinfunction "IO_L6P_T0_13_T20") (pintype "bidirectional"))
    )
    (net (code "110") (name "unconnected-(D7A-IO_L12N_T1_MRCC_13-PadW19)") (class "Default")
      (node (ref "D7") (pin "W19") (pinfunction "IO_L12N_T1_MRCC_13_W19") (pintype "bidirectional+no_connect"))
    )
    (net (code "111") (name "unconnected-(D7A-IO_L13N_T2_MRCC_13-PadY19)") (class "Default")
      (node (ref "D7") (pin "Y19") (pinfunction "IO_L13N_T2_MRCC_13_Y19") (pintype "bidirectional+no_connect"))
    )
    (net (code "112") (name "unconnected-(D7A-IO_L13P_T2_MRCC_13-PadY18)") (class "Default")
      (node (ref "D7") (pin "Y18") (pinfunction "IO_L13P_T2_MRCC_13_Y18") (pintype "bidirectional"))
    )
    (net (code "113") (name "unconnected-(D7A-IO_L24P_T3_13-PadT15)") (class "Default")
      (node (ref "D7") (pin "T15") (pinfunction "IO_L24P_T3_13_T15") (pintype "bidirectional"))
    )
    (net (code "114") (name "unconnected-(D7D-IO_L9P_T1_DQS_16-PadH14)") (class "Default")
      (node (ref "D7") (pin "H14") (pinfunction "IO_L9P_T1_DQS_16_H14") (pintype "bidirectional"))
    )
    (net (code "115") (name "unconnected-(D7D-IO_L12N_T1_MRCC_16-PadD11)") (class "Default")
      (node (ref "D7") (pin "D11") (pinfunction "IO_L12N_T1_MRCC_16_D11") (pintype "bidirectional"))
    )
    (net (code "116") (name "unconnected-(D7D-IO_L12P_T1_MRCC_16-PadE11)") (class "Default")
      (node (ref "D7") (pin "E11") (pinfunction "IO_L12P_T1_MRCC_16_E11") (pintype "bidirectional"))
    )
    (net (code "117") (name "unconnected-(X5-Pad24)") (class "Default")
      (node (ref "X5") (pin "24") (pinfunction "24_24") (pintype "passive"))
    )
    (net (code "118") (name "unconnected-(X5-Pad26)") (class "Default")
      (node (ref "X5") (pin "26") (pinfunction "26_26") (pintype "passive"))
    )
    (net (code "119") (name "unconnected-(X5-Pad28)") (class "Default")
      (node (ref "X5") (pin "28") (pinfunction "28_28") (pintype "passive"))
    )
    (net (code "120") (name "unconnected-(X5-Pad39)") (class "Default")
      (node (ref "X5") (pin "39") (pinfunction "39_39") (pintype "passive"))
    )
    (net (code "121") (name "unconnected-(X5-Pad40)") (class "Default")
      (node (ref "X5") (pin "40") (pinfunction "40_40") (pintype "passive"))
    )
    (net (code "122") (name "unconnected-(X5-Pad55)") (class "Default")
      (node (ref "X5") (pin "55") (pinfunction "55_55") (pintype "passive"))
    )
    (net (code "123") (name "unconnected-(X5-Pad58)") (class "Default")
      (node (ref "X5") (pin "58") (pinfunction "58_58") (pintype "passive"))
    )
    (net (code "124") (name "unconnected-(X5B-23-Pad87)") (class "Default")
      (node (ref "X5") (pin "87") (pinfunction "23_87") (pintype "passive"))
    )
    (net (code "125") (name "unconnected-(X5B-25-Pad89)") (class "Default")
      (node (ref "X5") (pin "89") (pinfunction "25_89") (pintype "passive"))
    )
    (net (code "126") (name "unconnected-(X5B-27-Pad91)") (class "Default")
      (node (ref "X5") (pin "91") (pinfunction "27_91") (pintype "passive"))
    )
    (net (code "127") (name "unconnected-(X5B-39-Pad103)") (class "Default")
      (node (ref "X5") (pin "103") (pinfunction "39_103") (pintype "passive"))
    )
    (net (code "128") (name "unconnected-(X5B-40-Pad104)") (class "Default")
      (node (ref "X5") (pin "104") (pinfunction "40_104") (pintype "passive"))
    )
    (net (code "129") (name "unconnected-(X5B-56-Pad120)") (class "Default")
      (node (ref "X5") (pin "120") (pinfunction "56_120") (pintype "passive"))
    )
    (net (code "130") (name "unconnected-(X5B-57-Pad121)") (class "Default")
      (node (ref "X5") (pin "121") (pinfunction "57_121") (pintype "passive"))
    )
  )
)
